# USB-NSTr_v3.net
KiCad netlist of a schematic drawn in Altium Designer
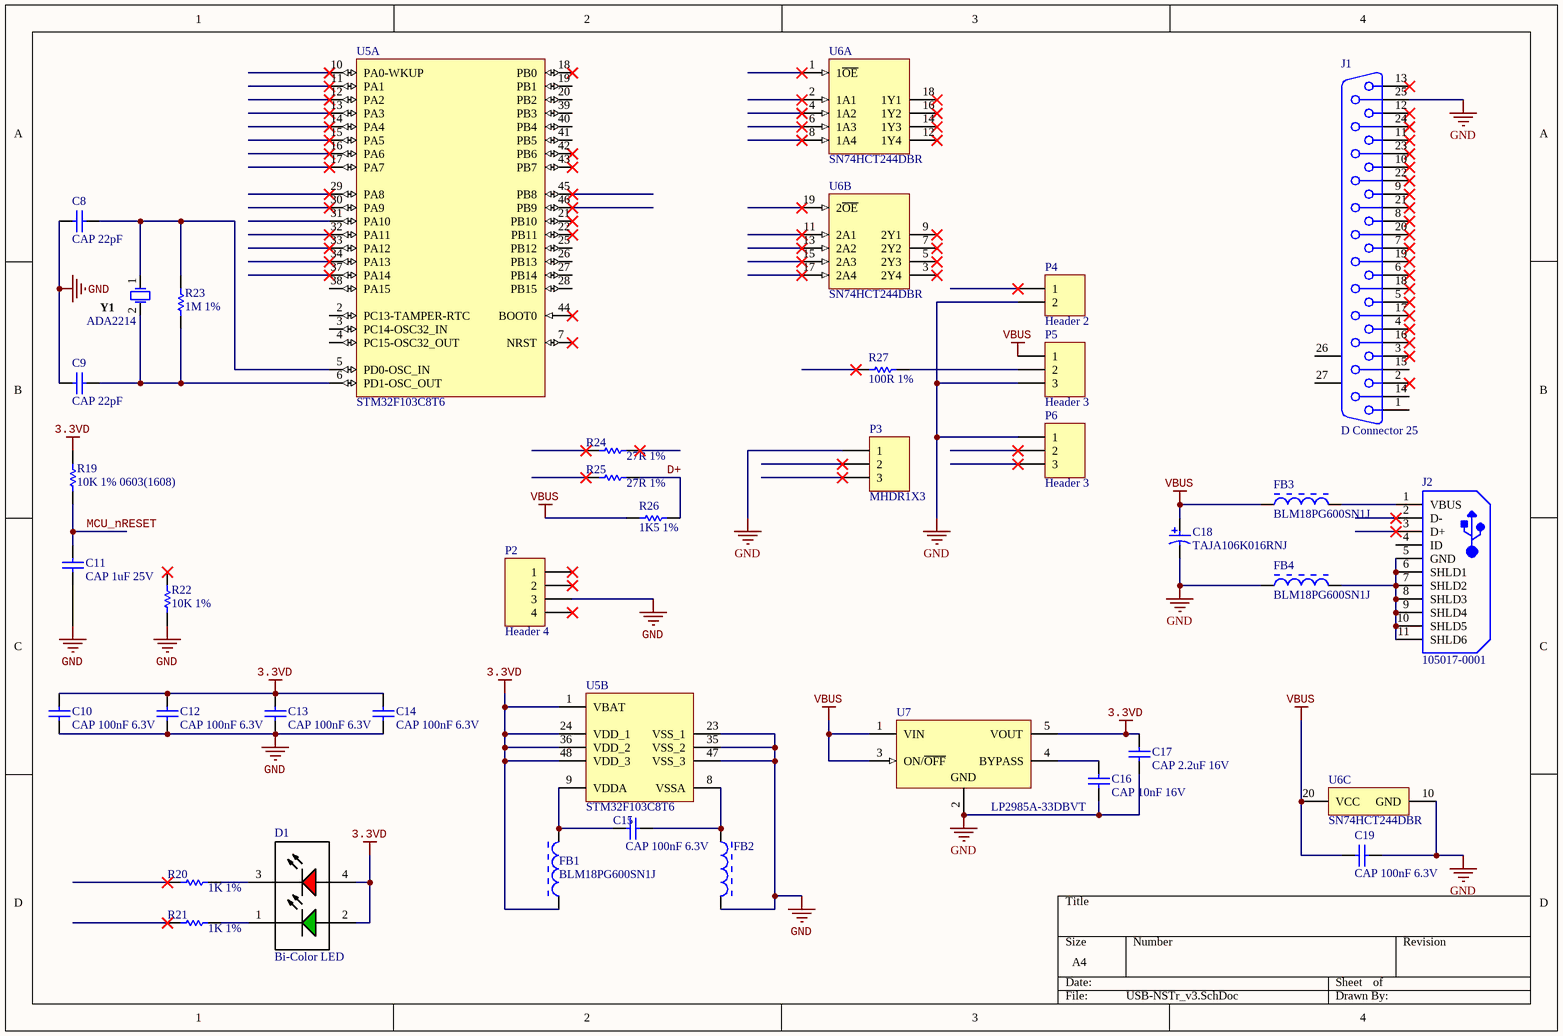
[diagram p0: USB-NSTr_v3.SchDoc]

(export (version "E")
  (design (tool "Eeschema 10.0.6"))
  (components
    (comp (ref "C8")
      (value "CAP 22pF")
      (footprint "CAPC0603(1608)100_N")
      (description "CAP 22pF 16V ±10% 0603 (1608 Metric) Thickness 1mm SMD")
      (fields (field (name "TOLERANCE") "Â±10%"))
      (libsource (lib "Altium Content Vault") (part "CAP"))
    )
    (comp (ref "C9")
      (value "CAP 22pF")
      (footprint "CAPC0603(1608)100_N")
      (description "CAP 22pF 16V ±10% 0603 (1608 Metric) Thickness 1mm SMD")
      (fields (field (name "TOLERANCE") "Â±10%"))
      (libsource (lib "Altium Content Vault") (part "CAP"))
    )
    (comp (ref "C10")
      (value "CAP 100nF 6.3V")
      (footprint "CAPC0603(1608)100_N")
      (description "CAP 100nF 6.3V ±10% 0603 (1608 Metric) Thickness 1mm SMD")
      (fields (field (name "TOLERANCE") "Â±10%"))
      (libsource (lib "Altium Content Vault") (part "CAP"))
    )
    (comp (ref "C11")
      (value "CAP 1uF 25V")
      (footprint "CAPC0603(1608)100_N")
      (description "CAP 1uF 25V ±20% 0603 (1608 Metric) Thickness 1mm SMD")
      (fields (field (name "TOLERANCE") "Â±20%"))
      (libsource (lib "Altium Content Vault") (part "CAP"))
    )
    (comp (ref "C12")
      (value "CAP 100nF 6.3V")
      (footprint "CAPC0603(1608)100_N")
      (description "CAP 100nF 6.3V ±10% 0603 (1608 Metric) Thickness 1mm SMD")
      (fields (field (name "TOLERANCE") "Â±10%"))
      (libsource (lib "Altium Content Vault") (part "CAP"))
    )
    (comp (ref "C13")
      (value "CAP 100nF 6.3V")
      (footprint "CAPC0603(1608)100_N")
      (description "CAP 100nF 6.3V ±10% 0603 (1608 Metric) Thickness 1mm SMD")
      (fields (field (name "TOLERANCE") "Â±10%"))
      (libsource (lib "Altium Content Vault") (part "CAP"))
    )
    (comp (ref "C14")
      (value "CAP 100nF 6.3V")
      (footprint "CAPC0603(1608)100_N")
      (description "CAP 100nF 6.3V ±10% 0603 (1608 Metric) Thickness 1mm SMD")
      (fields (field (name "TOLERANCE") "Â±10%"))
      (libsource (lib "Altium Content Vault") (part "CAP"))
    )
    (comp (ref "C15")
      (value "CAP 100nF 6.3V")
      (footprint "CAPC0603(1608)100_N")
      (description "CAP 100nF 6.3V ±10% 0603 (1608 Metric) Thickness 1mm SMD")
      (fields (field (name "TOLERANCE") "Â±10%"))
      (libsource (lib "Altium Content Vault") (part "CAP"))
    )
    (comp (ref "C16")
      (value "CAP 10nF 16V")
      (footprint "CAPC0603(1608)100_N")
      (description "CAP 10nF 16V ±5% 0603 (1608 Metric) Thickness 1mm SMD")
      (fields (field (name "TOLERANCE") "Â±5%"))
      (libsource (lib "Altium Content Vault") (part "CAP"))
    )
    (comp (ref "C17")
      (value "CAP 2.2uF 16V")
      (footprint "CAPC0603(1608)55_N")
      (description "CAP 2.2uF 16V ±20% 0603 (1608 Metric) Thickness 0.55mm SMD")
      (fields (field (name "TOLERANCE") "Â±20%"))
      (libsource (lib "Altium Content Vault") (part "CAP"))
    )
    (comp (ref "C18")
      (value "TAJA106K016RNJ")
      (footprint "CAPMP3217X18-T_V")
      (description "Standard Tantalum, 10 uF, +/- 10%, 16 V, -55 to 125 degC, 2-Pin SMD (1206), RoHS, Tape and Reel")
      (libsource (lib "Altium Content Vault") (part "CAP-P-2"))
    )
    (comp (ref "C19")
      (value "CAP 100nF 6.3V")
      (footprint "CAPC0603(1608)100_N")
      (description "CAP 100nF 6.3V ±10% 0603 (1608 Metric) Thickness 1mm SMD")
      (fields (field (name "TOLERANCE") "Â±10%"))
      (libsource (lib "Altium Content Vault") (part "CAP"))
    )
    (comp (ref "D1")
      (value "Bi-Color LED")
      (footprint "LED_Bi_Color_1204")
      (description "LED Indicator, Red / Green, 2 V, -40 to 100 degC, 4-Pin SMD, RoHS, Tape and Reel")
      (fields (field (name "MANUFACTURER") "Dialight"))
      (libsource (lib "MDR-36") (part "LED-RG-KAAK-4"))
    )
    (comp (ref "FB1")
      (value "BLM18PG600SN1J")
      (footprint "MURA-BLM18PG_KG-CHIP-2_V2")
      (fields (field (name "MANUFACTURER") "Murata"))
      (libsource (lib "Altium Content Vault") (part "MURA-FB-2"))
    )
    (comp (ref "FB2")
      (value "BLM18PG600SN1J")
      (footprint "MURA-BLM18PG_KG-CHIP-2_V2")
      (fields (field (name "MANUFACTURER") "Murata"))
      (libsource (lib "Altium Content Vault") (part "MURA-FB-2"))
    )
    (comp (ref "FB3")
      (value "BLM18PG600SN1J")
      (footprint "MURA-BLM18PG_KG-CHIP-2_V2")
      (fields (field (name "MANUFACTURER") "Murata"))
      (libsource (lib "Altium Content Vault") (part "MURA-FB-2"))
    )
    (comp (ref "FB4")
      (value "BLM18PG600SN1J")
      (footprint "MURA-BLM18PG_KG-CHIP-2_V2")
      (fields (field (name "MANUFACTURER") "Murata"))
      (libsource (lib "Altium Content Vault") (part "MURA-FB-2"))
    )
    (comp (ref "J1")
      (value "D Connector 25")
      (footprint "DB25-EDGE-Female-S")
      (description "Receptacle Assembly, 25 Position, Right Angle")
      (fields (field (name "PUBLISHER") "Altium Limited"))
      (libsource (lib "Miscellaneous Connectors") (part "D Connector 25"))
    )
    (comp (ref "J2")
      (value "105017-0001")
      (footprint "USB-MICRO-B_V")
      (fields (field (name "MANUFACTURER") "Molex"))
      (libsource (lib "Altium Content Vault") (part "USB-5-6SHLD"))
    )
    (comp (ref "P2")
      (value "Header 4")
      (footprint "PH2.0-LI-4P")
      (description "Header, 4-Pin")
      (fields (field (name "PUBLISHER") "Altium Limited"))
      (libsource (lib "Miscellaneous Connectors") (part "Header 4"))
    )
    (comp (ref "P3")
      (value "MHDR1X3")
      (footprint "HDR1X3")
      (description "Header, 3-Pin")
      (fields (field (name "PUBLISHER") "Altium Limited"))
      (libsource (lib "Miscellaneous Connectors") (part "MHDR1X3"))
    )
    (comp (ref "P4")
      (value "Header 2")
      (footprint "HDR1X2")
      (description "Header, 2-Pin")
      (fields (field (name "PUBLISHER") "Altium Limited"))
      (libsource (lib "Miscellaneous Connectors") (part "Header 2"))
    )
    (comp (ref "P5")
      (value "Header 3")
      (footprint "HDR1X3")
      (description "Header, 3-Pin")
      (fields (field (name "PUBLISHER") "Altium Limited"))
      (libsource (lib "Miscellaneous Connectors") (part "Header 3"))
    )
    (comp (ref "P6")
      (value "Header 3")
      (footprint "HDR1X3")
      (description "Header, 3-Pin")
      (fields (field (name "PUBLISHER") "Altium Limited"))
      (libsource (lib "Miscellaneous Connectors") (part "Header 3"))
    )
    (comp (ref "R19")
      (value "10K 1% 0603(1608)")
      (footprint "RESC0603(1608)_N")
      (description "10K 0.1W 1% 0603 (1608 Metric)  SMD")
      (fields (field (name "POWER") "0.1 W") (field (name "TOLERANCE") "1 %"))
      (libsource (lib "Altium Content Vault") (part "RES"))
    )
    (comp (ref "R20")
      (value "1K 1%")
      (footprint "RESC0603(1608)_N")
      (description "1K 0.1W 1% 0603 (1608 Metric)  SMD")
      (fields (field (name "TOLERANCE") "1 %") (field (name "POWER") "0.1 W"))
      (libsource (lib "Altium Content Vault") (part "RES"))
    )
    (comp (ref "R21")
      (value "1K 1%")
      (footprint "RESC0603(1608)_N")
      (description "1K 0.1W 1% 0603 (1608 Metric)  SMD")
      (fields (field (name "TOLERANCE") "1 %") (field (name "POWER") "0.1 W"))
      (libsource (lib "Altium Content Vault") (part "RES"))
    )
    (comp (ref "R22")
      (value "10K 1%")
      (footprint "RESC0603(1608)_N")
      (description "10K 0.1W 1% 0603 (1608 Metric)  SMD")
      (fields (field (name "POWER") "0.1 W") (field (name "TOLERANCE") "1 %"))
      (libsource (lib "Altium Content Vault") (part "RES"))
    )
    (comp (ref "R23")
      (value "1M 1%")
      (footprint "RESC0603(1608)_N")
      (description "1M 0.1W 1% 0603 (1608 Metric)  SMD")
      (fields (field (name "POWER") "0.1 W") (field (name "TOLERANCE") "1 %"))
      (libsource (lib "Altium Content Vault") (part "RES"))
    )
    (comp (ref "R24")
      (value "27R 1%")
      (footprint "RESC0603(1608)_N")
      (description "27R 0.1W 1% 0603 (1608 Metric)  SMD")
      (fields (field (name "TOLERANCE") "1 %") (field (name "POWER") "0.1 W"))
      (libsource (lib "Altium Content Vault") (part "RES"))
    )
    (comp (ref "R25")
      (value "27R 1%")
      (footprint "RESC0603(1608)_N")
      (description "27R 0.1W 1% 0603 (1608 Metric)  SMD")
      (fields (field (name "TOLERANCE") "1 %") (field (name "POWER") "0.1 W"))
      (libsource (lib "Altium Content Vault") (part "RES"))
    )
    (comp (ref "R26")
      (value "1K5 1%")
      (footprint "RESC0805(2012)_N")
      (description "1K5 0.125W 1% 0805 (2012 Metric)  SMD")
      (fields (field (name "POWER") "0.125 W") (field (name "TOLERANCE") "1 %"))
      (libsource (lib "Altium Content Vault") (part "RES"))
    )
    (comp (ref "R27")
      (value "100R 1%")
      (footprint "RESC0603(1608)_N")
      (description "100R 0.1W 1% 0603 (1608 Metric)  SMD")
      (fields (field (name "TOLERANCE") "1 %") (field (name "POWER") "0.1 W"))
      (libsource (lib "Altium Content Vault") (part "RES"))
    )
    (comp (ref "U5")
      (value "STM32F103C8T6")
      (footprint "STM-LQFP48_N")
      (libsource (lib "Altium Content Vault") (part "MC-ARM-STM32F103X8_B-SQ48"))
    )
    (comp (ref "U6")
      (value "SN74HCT244DBR")
      (footprint "DB0020A_N")
      (description "Octal Buffers And Line Drivers With 3-State Outputs, DB0020A, LARGE T&R")
      (fields
        (field (name "MANUFACTURER") "Texas Instruments")
        (field (name "GENERIC PART NUMBER") "SN74HCT244")
      )
      (libsource (lib "Altium Content Vault") (part "TI-SN54_74-XX020A-20"))
    )
    (comp (ref "U7")
      (value "LP2985A-33DBVT")
      (footprint "DBV0005A_N")
      (fields (field (name "MANUFACTURER") "Texas Instruments"))
      (libsource (lib "Altium Content Vault") (part "TI-LP2985_A-10DBV5"))
    )
    (comp (ref "Y1")
      (value "ADA2214")
      (footprint "ADAI-THHF-49S3")
      (description "Crystal, 12 MHz, 18 pF, 30 PPM, -20 to 70 degC, 2-Pin THD, RoHS")
      (libsource (lib "Altium Content Vault") (part "XTAL-1-2-2"))
    )
  )
  (nets
    (net (code "1") (name "/D+") (class "Default")
      (node (ref "R25") (pin "2") (pinfunction "2_2") (pintype "passive"))
      (node (ref "R26") (pin "1") (pinfunction "1_1") (pintype "passive"))
    )
    (net (code "2") (name "/MCU_nRESET") (class "Default")
      (node (ref "C11") (pin "2") (pinfunction "2_2") (pintype "passive"))
      (node (ref "R19") (pin "1") (pinfunction "1_1") (pintype "passive"))
    )
    (net (code "3") (name "3.3VD") (class "Default")
      (node (ref "C10") (pin "2") (pinfunction "2_2") (pintype "passive"))
      (node (ref "C12") (pin "2") (pinfunction "2_2") (pintype "passive"))
      (node (ref "C13") (pin "2") (pinfunction "2_2") (pintype "passive"))
      (node (ref "C14") (pin "2") (pinfunction "2_2") (pintype "passive"))
      (node (ref "C17") (pin "2") (pinfunction "2_2") (pintype "passive"))
      (node (ref "D1") (pin "2") (pinfunction "Green-A_2") (pintype "passive"))
      (node (ref "D1") (pin "4") (pinfunction "Red-A_4") (pintype "passive"))
      (node (ref "FB1") (pin "1") (pinfunction "1_1") (pintype "passive"))
      (node (ref "R19") (pin "2") (pinfunction "2_2") (pintype "passive"))
      (node (ref "U5") (pin "1") (pinfunction "VBAT_1") (pintype "power_in"))
      (node (ref "U5") (pin "24") (pinfunction "VDD_1_24") (pintype "power_in"))
      (node (ref "U5") (pin "36") (pinfunction "VDD_2_36") (pintype "power_in"))
      (node (ref "U5") (pin "48") (pinfunction "VDD_3_48") (pintype "power_in"))
      (node (ref "U7") (pin "5") (pinfunction "VOUT_5") (pintype "power_in"))
    )
    (net (code "4") (name "GND") (class "Default")
      (node (ref "C10") (pin "1") (pinfunction "1_1") (pintype "passive"))
      (node (ref "C11") (pin "1") (pinfunction "1_1") (pintype "passive"))
      (node (ref "C12") (pin "1") (pinfunction "1_1") (pintype "passive"))
      (node (ref "C13") (pin "1") (pinfunction "1_1") (pintype "passive"))
      (node (ref "C14") (pin "1") (pinfunction "1_1") (pintype "passive"))
      (node (ref "C16") (pin "1") (pinfunction "1_1") (pintype "passive"))
      (node (ref "C17") (pin "1") (pinfunction "1_1") (pintype "passive"))
      (node (ref "C18") (pin "2") (pinfunction "2_2") (pintype "passive"))
      (node (ref "C19") (pin "1") (pinfunction "1_1") (pintype "passive"))
      (node (ref "C8") (pin "2") (pinfunction "2_2") (pintype "passive"))
      (node (ref "C9") (pin "2") (pinfunction "2_2") (pintype "passive"))
      (node (ref "FB2") (pin "2") (pinfunction "2_2") (pintype "passive"))
      (node (ref "FB4") (pin "1") (pinfunction "1_1") (pintype "passive"))
      (node (ref "J1") (pin "25") (pinfunction "25_25") (pintype "passive"))
      (node (ref "P2") (pin "3") (pinfunction "3_3") (pintype "passive"))
      (node (ref "P3") (pin "1") (pinfunction "1_1") (pintype "passive"))
      (node (ref "P4") (pin "2") (pinfunction "2_2") (pintype "passive"))
      (node (ref "P5") (pin "3") (pinfunction "3_3") (pintype "passive"))
      (node (ref "P6") (pin "1") (pinfunction "1_1") (pintype "passive"))
      (node (ref "R22") (pin "1") (pinfunction "1_1") (pintype "passive"))
      (node (ref "U5") (pin "23") (pinfunction "VSS_1_23") (pintype "power_in"))
      (node (ref "U5") (pin "35") (pinfunction "VSS_2_35") (pintype "power_in"))
      (node (ref "U5") (pin "47") (pinfunction "VSS_3_47") (pintype "power_in"))
      (node (ref "U6") (pin "10") (pinfunction "GND_10") (pintype "power_in"))
      (node (ref "U7") (pin "2") (pinfunction "GND_2") (pintype "power_in"))
    )
    (net (code "5") (name "Net-(D1-Green-C)") (class "Default")
      (node (ref "D1") (pin "1") (pinfunction "Green-C_1") (pintype "passive"))
      (node (ref "R21") (pin "2") (pinfunction "2_2") (pintype "passive"))
    )
    (net (code "6") (name "Net-(D1-Red-C)") (class "Default")
      (node (ref "D1") (pin "3") (pinfunction "Red-C_3") (pintype "passive"))
      (node (ref "R20") (pin "2") (pinfunction "2_2") (pintype "passive"))
    )
    (net (code "7") (name "Net-(J2-GND)") (class "Default")
      (node (ref "FB4") (pin "2") (pinfunction "2_2") (pintype "passive"))
      (node (ref "J2") (pin "10") (pinfunction "SHLD5_10") (pintype "passive"))
      (node (ref "J2") (pin "11") (pinfunction "SHLD6_11") (pintype "passive"))
      (node (ref "J2") (pin "5") (pinfunction "GND_5") (pintype "passive"))
      (node (ref "J2") (pin "6") (pinfunction "SHLD1_6") (pintype "passive"))
      (node (ref "J2") (pin "7") (pinfunction "SHLD2_7") (pintype "passive"))
      (node (ref "J2") (pin "8") (pinfunction "SHLD3_8") (pintype "passive"))
      (node (ref "J2") (pin "9") (pinfunction "SHLD4_9") (pintype "passive"))
    )
    (net (code "8") (name "Net-(J2-VBUS)") (class "Default")
      (node (ref "FB3") (pin "2") (pinfunction "2_2") (pintype "passive"))
      (node (ref "J2") (pin "1") (pinfunction "VBUS_1") (pintype "passive"))
    )
    (net (code "9") (name "Net-(P5-Pad2)") (class "Default")
      (node (ref "P5") (pin "2") (pinfunction "2_2") (pintype "passive"))
      (node (ref "R27") (pin "2") (pinfunction "2_2") (pintype "passive"))
    )
    (net (code "10") (name "Net-(U5A-PD0-OSC_IN)") (class "Default")
      (node (ref "C8") (pin "1") (pinfunction "1_1") (pintype "passive"))
      (node (ref "R23") (pin "2") (pinfunction "2_2") (pintype "passive"))
      (node (ref "U5") (pin "5") (pinfunction "PD0-OSC_IN_5") (pintype "bidirectional"))
      (node (ref "Y1") (pin "1") (pinfunction "1_1") (pintype "passive"))
    )
    (net (code "11") (name "Net-(U5A-PD1-OSC_OUT)") (class "Default")
      (node (ref "C9") (pin "1") (pinfunction "1_1") (pintype "passive"))
      (node (ref "R23") (pin "1") (pinfunction "1_1") (pintype "passive"))
      (node (ref "U5") (pin "6") (pinfunction "PD1-OSC_OUT_6") (pintype "bidirectional"))
      (node (ref "Y1") (pin "2") (pinfunction "2_2") (pintype "passive"))
    )
    (net (code "12") (name "Net-(U5B-VDDA)") (class "Default")
      (node (ref "C15") (pin "2") (pinfunction "2_2") (pintype "passive"))
      (node (ref "FB1") (pin "2") (pinfunction "2_2") (pintype "passive"))
      (node (ref "U5") (pin "9") (pinfunction "VDDA_9") (pintype "power_in"))
    )
    (net (code "13") (name "Net-(U5B-VSSA)") (class "Default")
      (node (ref "C15") (pin "1") (pinfunction "1_1") (pintype "passive"))
      (node (ref "FB2") (pin "1") (pinfunction "1_1") (pintype "passive"))
      (node (ref "U5") (pin "8") (pinfunction "VSSA_8") (pintype "power_in"))
    )
    (net (code "14") (name "Net-(U7-BYPASS)") (class "Default")
      (node (ref "C16") (pin "2") (pinfunction "2_2") (pintype "passive"))
      (node (ref "U7") (pin "4") (pinfunction "BYPASS_4") (pintype "passive"))
    )
    (net (code "15") (name "VBUS") (class "Default")
      (node (ref "C18") (pin "1") (pinfunction "1_1") (pintype "passive"))
      (node (ref "C19") (pin "2") (pinfunction "2_2") (pintype "passive"))
      (node (ref "FB3") (pin "1") (pinfunction "1_1") (pintype "passive"))
      (node (ref "P5") (pin "1") (pinfunction "1_1") (pintype "passive"))
      (node (ref "R26") (pin "2") (pinfunction "2_2") (pintype "passive"))
      (node (ref "U6") (pin "20") (pinfunction "VCC_20") (pintype "power_in"))
      (node (ref "U7") (pin "1") (pinfunction "VIN_1") (pintype "power_in"))
      (node (ref "U7") (pin "3") (pinfunction "ON/~{OFF}_3") (pintype "input"))
    )
    (net (code "16") (name "unconnected-(J1-MH1-Pad26)") (class "Default")
      (node (ref "J1") (pin "26") (pinfunction "MH1_26") (pintype "passive"))
    )
    (net (code "17") (name "unconnected-(J1-MH2-Pad27)") (class "Default")
      (node (ref "J1") (pin "27") (pinfunction "MH2_27") (pintype "passive"))
    )
    (net (code "18") (name "unconnected-(J1-Pad1)") (class "Default")
      (node (ref "J1") (pin "1") (pinfunction "1_1") (pintype "passive"))
    )
    (net (code "19") (name "unconnected-(J1-Pad2)") (class "Default")
      (node (ref "J1") (pin "2") (pinfunction "2_2") (pintype "passive+no_connect"))
    )
    (net (code "20") (name "unconnected-(J1-Pad3)") (class "Default")
      (node (ref "J1") (pin "3") (pinfunction "3_3") (pintype "passive+no_connect"))
    )
    (net (code "21") (name "unconnected-(J1-Pad4)") (class "Default")
      (node (ref "J1") (pin "4") (pinfunction "4_4") (pintype "passive+no_connect"))
    )
    (net (code "22") (name "unconnected-(J1-Pad5)") (class "Default")
      (node (ref "J1") (pin "5") (pinfunction "5_5") (pintype "passive+no_connect"))
    )
    (net (code "23") (name "unconnected-(J1-Pad6)") (class "Default")
      (node (ref "J1") (pin "6") (pinfunction "6_6") (pintype "passive+no_connect"))
    )
    (net (code "24") (name "unconnected-(J1-Pad7)") (class "Default")
      (node (ref "J1") (pin "7") (pinfunction "7_7") (pintype "passive+no_connect"))
    )
    (net (code "25") (name "unconnected-(J1-Pad8)") (class "Default")
      (node (ref "J1") (pin "8") (pinfunction "8_8") (pintype "passive+no_connect"))
    )
    (net (code "26") (name "unconnected-(J1-Pad9)") (class "Default")
      (node (ref "J1") (pin "9") (pinfunction "9_9") (pintype "passive+no_connect"))
    )
    (net (code "27") (name "unconnected-(J1-Pad10)") (class "Default")
      (node (ref "J1") (pin "10") (pinfunction "10_10") (pintype "passive+no_connect"))
    )
    (net (code "28") (name "unconnected-(J1-Pad11)") (class "Default")
      (node (ref "J1") (pin "11") (pinfunction "11_11") (pintype "passive+no_connect"))
    )
    (net (code "29") (name "unconnected-(J1-Pad12)") (class "Default")
      (node (ref "J1") (pin "12") (pinfunction "12_12") (pintype "passive+no_connect"))
    )
    (net (code "30") (name "unconnected-(J1-Pad13)") (class "Default")
      (node (ref "J1") (pin "13") (pinfunction "13_13") (pintype "passive+no_connect"))
    )
    (net (code "31") (name "unconnected-(J1-Pad14)") (class "Default")
      (node (ref "J1") (pin "14") (pinfunction "14_14") (pintype "passive"))
    )
    (net (code "32") (name "unconnected-(J1-Pad15)") (class "Default")
      (node (ref "J1") (pin "15") (pinfunction "15_15") (pintype "passive"))
    )
    (net (code "33") (name "unconnected-(J1-Pad16)") (class "Default")
      (node (ref "J1") (pin "16") (pinfunction "16_16") (pintype "passive+no_connect"))
    )
    (net (code "34") (name "unconnected-(J1-Pad17)") (class "Default")
      (node (ref "J1") (pin "17") (pinfunction "17_17") (pintype "passive+no_connect"))
    )
    (net (code "35") (name "unconnected-(J1-Pad18)") (class "Default")
      (node (ref "J1") (pin "18") (pinfunction "18_18") (pintype "passive+no_connect"))
    )
    (net (code "36") (name "unconnected-(J1-Pad19)") (class "Default")
      (node (ref "J1") (pin "19") (pinfunction "19_19") (pintype "passive+no_connect"))
    )
    (net (code "37") (name "unconnected-(J1-Pad20)") (class "Default")
      (node (ref "J1") (pin "20") (pinfunction "20_20") (pintype "passive+no_connect"))
    )
    (net (code "38") (name "unconnected-(J1-Pad21)") (class "Default")
      (node (ref "J1") (pin "21") (pinfunction "21_21") (pintype "passive+no_connect"))
    )
    (net (code "39") (name "unconnected-(J1-Pad22)") (class "Default")
      (node (ref "J1") (pin "22") (pinfunction "22_22") (pintype "passive+no_connect"))
    )
    (net (code "40") (name "unconnected-(J1-Pad23)") (class "Default")
      (node (ref "J1") (pin "23") (pinfunction "23_23") (pintype "passive+no_connect"))
    )
    (net (code "41") (name "unconnected-(J1-Pad24)") (class "Default")
      (node (ref "J1") (pin "24") (pinfunction "24_24") (pintype "passive+no_connect"))
    )
    (net (code "42") (name "unconnected-(J2-D+-Pad3)") (class "Default")
      (node (ref "J2") (pin "3") (pinfunction "D+_3") (pintype "passive+no_connect"))
    )
    (net (code "43") (name "unconnected-(J2-D--Pad2)") (class "Default")
      (node (ref "J2") (pin "2") (pinfunction "D-_2") (pintype "passive+no_connect"))
    )
    (net (code "44") (name "unconnected-(J2-ID-Pad4)") (class "Default")
      (node (ref "J2") (pin "4") (pinfunction "ID_4") (pintype "passive"))
    )
    (net (code "45") (name "unconnected-(P2-Pad1)") (class "Default")
      (node (ref "P2") (pin "1") (pinfunction "1_1") (pintype "passive+no_connect"))
    )
    (net (code "46") (name "unconnected-(P2-Pad2)") (class "Default")
      (node (ref "P2") (pin "2") (pinfunction "2_2") (pintype "passive+no_connect"))
    )
    (net (code "47") (name "unconnected-(P2-Pad4)") (class "Default")
      (node (ref "P2") (pin "4") (pinfunction "4_4") (pintype "passive+no_connect"))
    )
    (net (code "48") (name "unconnected-(P3-Pad2)") (class "Default")
      (node (ref "P3") (pin "2") (pinfunction "2_2") (pintype "passive+no_connect"))
    )
    (net (code "49") (name "unconnected-(P3-Pad3)") (class "Default")
      (node (ref "P3") (pin "3") (pinfunction "3_3") (pintype "passive+no_connect"))
    )
    (net (code "50") (name "unconnected-(P4-Pad1)") (class "Default")
      (node (ref "P4") (pin "1") (pinfunction "1_1") (pintype "passive+no_connect"))
    )
    (net (code "51") (name "unconnected-(P6-Pad2)") (class "Default")
      (node (ref "P6") (pin "2") (pinfunction "2_2") (pintype "passive+no_connect"))
    )
    (net (code "52") (name "unconnected-(P6-Pad3)") (class "Default")
      (node (ref "P6") (pin "3") (pinfunction "3_3") (pintype "passive+no_connect"))
    )
    (net (code "53") (name "unconnected-(R20-Pad1)") (class "Default")
      (node (ref "R20") (pin "1") (pinfunction "1_1") (pintype "passive+no_connect"))
    )
    (net (code "54") (name "unconnected-(R21-Pad1)") (class "Default")
      (node (ref "R21") (pin "1") (pinfunction "1_1") (pintype "passive+no_connect"))
    )
    (net (code "55") (name "unconnected-(R22-Pad2)") (class "Default")
      (node (ref "R22") (pin "2") (pinfunction "2_2") (pintype "passive+no_connect"))
    )
    (net (code "56") (name "unconnected-(R24-Pad1)") (class "Default")
      (node (ref "R24") (pin "1") (pinfunction "1_1") (pintype "passive+no_connect"))
    )
    (net (code "57") (name "unconnected-(R24-Pad2)") (class "Default")
      (node (ref "R24") (pin "2") (pinfunction "2_2") (pintype "passive+no_connect"))
    )
    (net (code "58") (name "unconnected-(R25-Pad1)") (class "Default")
      (node (ref "R25") (pin "1") (pinfunction "1_1") (pintype "passive+no_connect"))
    )
    (net (code "59") (name "unconnected-(R27-Pad1)") (class "Default")
      (node (ref "R27") (pin "1") (pinfunction "1_1") (pintype "passive+no_connect"))
    )
    (net (code "60") (name "unconnected-(U5A-BOOT0-Pad44)") (class "Default")
      (node (ref "U5") (pin "44") (pinfunction "BOOT0_44") (pintype "input+no_connect"))
    )
    (net (code "61") (name "unconnected-(U5A-NRST-Pad7)") (class "Default")
      (node (ref "U5") (pin "7") (pinfunction "NRST_7") (pintype "bidirectional+no_connect"))
    )
    (net (code "62") (name "unconnected-(U5A-PA0-WKUP-Pad10)") (class "Default")
      (node (ref "U5") (pin "10") (pinfunction "PA0-WKUP_10") (pintype "bidirectional+no_connect"))
    )
    (net (code "63") (name "unconnected-(U5A-PA1-Pad11)") (class "Default")
      (node (ref "U5") (pin "11") (pinfunction "PA1_11") (pintype "bidirectional+no_connect"))
    )
    (net (code "64") (name "unconnected-(U5A-PA2-Pad12)") (class "Default")
      (node (ref "U5") (pin "12") (pinfunction "PA2_12") (pintype "bidirectional+no_connect"))
    )
    (net (code "65") (name "unconnected-(U5A-PA3-Pad13)") (class "Default")
      (node (ref "U5") (pin "13") (pinfunction "PA3_13") (pintype "bidirectional+no_connect"))
    )
    (net (code "66") (name "unconnected-(U5A-PA4-Pad14)") (class "Default")
      (node (ref "U5") (pin "14") (pinfunction "PA4_14") (pintype "bidirectional+no_connect"))
    )
    (net (code "67") (name "unconnected-(U5A-PA5-Pad15)") (class "Default")
      (node (ref "U5") (pin "15") (pinfunction "PA5_15") (pintype "bidirectional+no_connect"))
    )
    (net (code "68") (name "unconnected-(U5A-PA6-Pad16)") (class "Default")
      (node (ref "U5") (pin "16") (pinfunction "PA6_16") (pintype "bidirectional+no_connect"))
    )
    (net (code "69") (name "unconnected-(U5A-PA7-Pad17)") (class "Default")
      (node (ref "U5") (pin "17") (pinfunction "PA7_17") (pintype "bidirectional+no_connect"))
    )
    (net (code "70") (name "unconnected-(U5A-PA8-Pad29)") (class "Default")
      (node (ref "U5") (pin "29") (pinfunction "PA8_29") (pintype "bidirectional+no_connect"))
    )
    (net (code "71") (name "unconnected-(U5A-PA9-Pad30)") (class "Default")
      (node (ref "U5") (pin "30") (pinfunction "PA9_30") (pintype "bidirectional+no_connect"))
    )
    (net (code "72") (name "unconnected-(U5A-PA10-Pad31)") (class "Default")
      (node (ref "U5") (pin "31") (pinfunction "PA10_31") (pintype "bidirectional"))
    )
    (net (code "73") (name "unconnected-(U5A-PA11-Pad32)") (class "Default")
      (node (ref "U5") (pin "32") (pinfunction "PA11_32") (pintype "bidirectional+no_connect"))
    )
    (net (code "74") (name "unconnected-(U5A-PA12-Pad33)") (class "Default")
      (node (ref "U5") (pin "33") (pinfunction "PA12_33") (pintype "bidirectional+no_connect"))
    )
    (net (code "75") (name "unconnected-(U5A-PA13-Pad34)") (class "Default")
      (node (ref "U5") (pin "34") (pinfunction "PA13_34") (pintype "bidirectional+no_connect"))
    )
    (net (code "76") (name "unconnected-(U5A-PA14-Pad37)") (class "Default")
      (node (ref "U5") (pin "37") (pinfunction "PA14_37") (pintype "bidirectional+no_connect"))
    )
    (net (code "77") (name "unconnected-(U5A-PA15-Pad38)") (class "Default")
      (node (ref "U5") (pin "38") (pinfunction "PA15_38") (pintype "bidirectional"))
    )
    (net (code "78") (name "unconnected-(U5A-PB0-Pad18)") (class "Default")
      (node (ref "U5") (pin "18") (pinfunction "PB0_18") (pintype "bidirectional+no_connect"))
    )
    (net (code "79") (name "unconnected-(U5A-PB1-Pad19)") (class "Default")
      (node (ref "U5") (pin "19") (pinfunction "PB1_19") (pintype "bidirectional"))
    )
    (net (code "80") (name "unconnected-(U5A-PB2-Pad20)") (class "Default")
      (node (ref "U5") (pin "20") (pinfunction "PB2_20") (pintype "bidirectional"))
    )
    (net (code "81") (name "unconnected-(U5A-PB3-Pad39)") (class "Default")
      (node (ref "U5") (pin "39") (pinfunction "PB3_39") (pintype "bidirectional"))
    )
    (net (code "82") (name "unconnected-(U5A-PB4-Pad40)") (class "Default")
      (node (ref "U5") (pin "40") (pinfunction "PB4_40") (pintype "bidirectional"))
    )
    (net (code "83") (name "unconnected-(U5A-PB5-Pad41)") (class "Default")
      (node (ref "U5") (pin "41") (pinfunction "PB5_41") (pintype "bidirectional"))
    )
    (net (code "84") (name "unconnected-(U5A-PB6-Pad42)") (class "Default")
      (node (ref "U5") (pin "42") (pinfunction "PB6_42") (pintype "bidirectional+no_connect"))
    )
    (net (code "85") (name "unconnected-(U5A-PB7-Pad43)") (class "Default")
      (node (ref "U5") (pin "43") (pinfunction "PB7_43") (pintype "bidirectional+no_connect"))
    )
    (net (code "86") (name "unconnected-(U5A-PB8-Pad45)") (class "Default")
      (node (ref "U5") (pin "45") (pinfunction "PB8_45") (pintype "bidirectional+no_connect"))
    )
    (net (code "87") (name "unconnected-(U5A-PB9-Pad46)") (class "Default")
      (node (ref "U5") (pin "46") (pinfunction "PB9_46") (pintype "bidirectional+no_connect"))
    )
    (net (code "88") (name "unconnected-(U5A-PB10-Pad21)") (class "Default")
      (node (ref "U5") (pin "21") (pinfunction "PB10_21") (pintype "bidirectional+no_connect"))
    )
    (net (code "89") (name "unconnected-(U5A-PB11-Pad22)") (class "Default")
      (node (ref "U5") (pin "22") (pinfunction "PB11_22") (pintype "bidirectional+no_connect"))
    )
    (net (code "90") (name "unconnected-(U5A-PB12-Pad25)") (class "Default")
      (node (ref "U5") (pin "25") (pinfunction "PB12_25") (pintype "bidirectional"))
    )
    (net (code "91") (name "unconnected-(U5A-PB13-Pad26)") (class "Default")
      (node (ref "U5") (pin "26") (pinfunction "PB13_26") (pintype "bidirectional"))
    )
    (net (code "92") (name "unconnected-(U5A-PB14-Pad27)") (class "Default")
      (node (ref "U5") (pin "27") (pinfunction "PB14_27") (pintype "bidirectional"))
    )
    (net (code "93") (name "unconnected-(U5A-PB15-Pad28)") (class "Default")
      (node (ref "U5") (pin "28") (pinfunction "PB15_28") (pintype "bidirectional"))
    )
    (net (code "94") (name "unconnected-(U5A-PC13-TAMPER-RTC-Pad2)") (class "Default")
      (node (ref "U5") (pin "2") (pinfunction "PC13-TAMPER-RTC_2") (pintype "bidirectional"))
    )
    (net (code "95") (name "unconnected-(U5A-PC14-OSC32_IN-Pad3)") (class "Default")
      (node (ref "U5") (pin "3") (pinfunction "PC14-OSC32_IN_3") (pintype "bidirectional"))
    )
    (net (code "96") (name "unconnected-(U5A-PC15-OSC32_OUT-Pad4)") (class "Default")
      (node (ref "U5") (pin "4") (pinfunction "PC15-OSC32_OUT_4") (pintype "bidirectional"))
    )
    (net (code "97") (name "unconnected-(U6A-1A1-Pad2)") (class "Default")
      (node (ref "U6") (pin "2") (pinfunction "1A1_2") (pintype "input+no_connect"))
    )
    (net (code "98") (name "unconnected-(U6A-1A2-Pad4)") (class "Default")
      (node (ref "U6") (pin "4") (pinfunction "1A2_4") (pintype "input+no_connect"))
    )
    (net (code "99") (name "unconnected-(U6A-1A3-Pad6)") (class "Default")
      (node (ref "U6") (pin "6") (pinfunction "1A3_6") (pintype "input+no_connect"))
    )
    (net (code "100") (name "unconnected-(U6A-1A4-Pad8)") (class "Default")
      (node (ref "U6") (pin "8") (pinfunction "1A4_8") (pintype "input+no_connect"))
    )
    (net (code "101") (name "unconnected-(U6A-1Y1-Pad18)") (class "Default")
      (node (ref "U6") (pin "18") (pinfunction "1Y1_18") (pintype "tri_state+no_connect"))
    )
    (net (code "102") (name "unconnected-(U6A-1Y2-Pad16)") (class "Default")
      (node (ref "U6") (pin "16") (pinfunction "1Y2_16") (pintype "tri_state+no_connect"))
    )
    (net (code "103") (name "unconnected-(U6A-1Y3-Pad14)") (class "Default")
      (node (ref "U6") (pin "14") (pinfunction "1Y3_14") (pintype "tri_state+no_connect"))
    )
    (net (code "104") (name "unconnected-(U6A-1Y4-Pad12)") (class "Default")
      (node (ref "U6") (pin "12") (pinfunction "1Y4_12") (pintype "tri_state+no_connect"))
    )
    (net (code "105") (name "unconnected-(U6A-1~{OE}-Pad1)") (class "Default")
      (node (ref "U6") (pin "1") (pinfunction "1~{OE}_1") (pintype "input+no_connect"))
    )
    (net (code "106") (name "unconnected-(U6B-2A1-Pad11)") (class "Default")
      (node (ref "U6") (pin "11") (pinfunction "2A1_11") (pintype "input+no_connect"))
    )
    (net (code "107") (name "unconnected-(U6B-2A2-Pad13)") (class "Default")
      (node (ref "U6") (pin "13") (pinfunction "2A2_13") (pintype "input+no_connect"))
    )
    (net (code "108") (name "unconnected-(U6B-2A3-Pad15)") (class "Default")
      (node (ref "U6") (pin "15") (pinfunction "2A3_15") (pintype "input+no_connect"))
    )
    (net (code "109") (name "unconnected-(U6B-2A4-Pad17)") (class "Default")
      (node (ref "U6") (pin "17") (pinfunction "2A4_17") (pintype "input+no_connect"))
    )
    (net (code "110") (name "unconnected-(U6B-2Y1-Pad9)") (class "Default")
      (node (ref "U6") (pin "9") (pinfunction "2Y1_9") (pintype "tri_state+no_connect"))
    )
    (net (code "111") (name "unconnected-(U6B-2Y2-Pad7)") (class "Default")
      (node (ref "U6") (pin "7") (pinfunction "2Y2_7") (pintype "tri_state+no_connect"))
    )
    (net (code "112") (name "unconnected-(U6B-2Y3-Pad5)") (class "Default")
      (node (ref "U6") (pin "5") (pinfunction "2Y3_5") (pintype "tri_state+no_connect"))
    )
    (net (code "113") (name "unconnected-(U6B-2Y4-Pad3)") (class "Default")
      (node (ref "U6") (pin "3") (pinfunction "2Y4_3") (pintype "tri_state+no_connect"))
    )
    (net (code "114") (name "unconnected-(U6B-2~{OE}-Pad19)") (class "Default")
      (node (ref "U6") (pin "19") (pinfunction "2~{OE}_19") (pintype "input+no_connect"))
    )
  )
)
